# lt1345.net
KiCad netlist of a schematic drawn in EAGLE
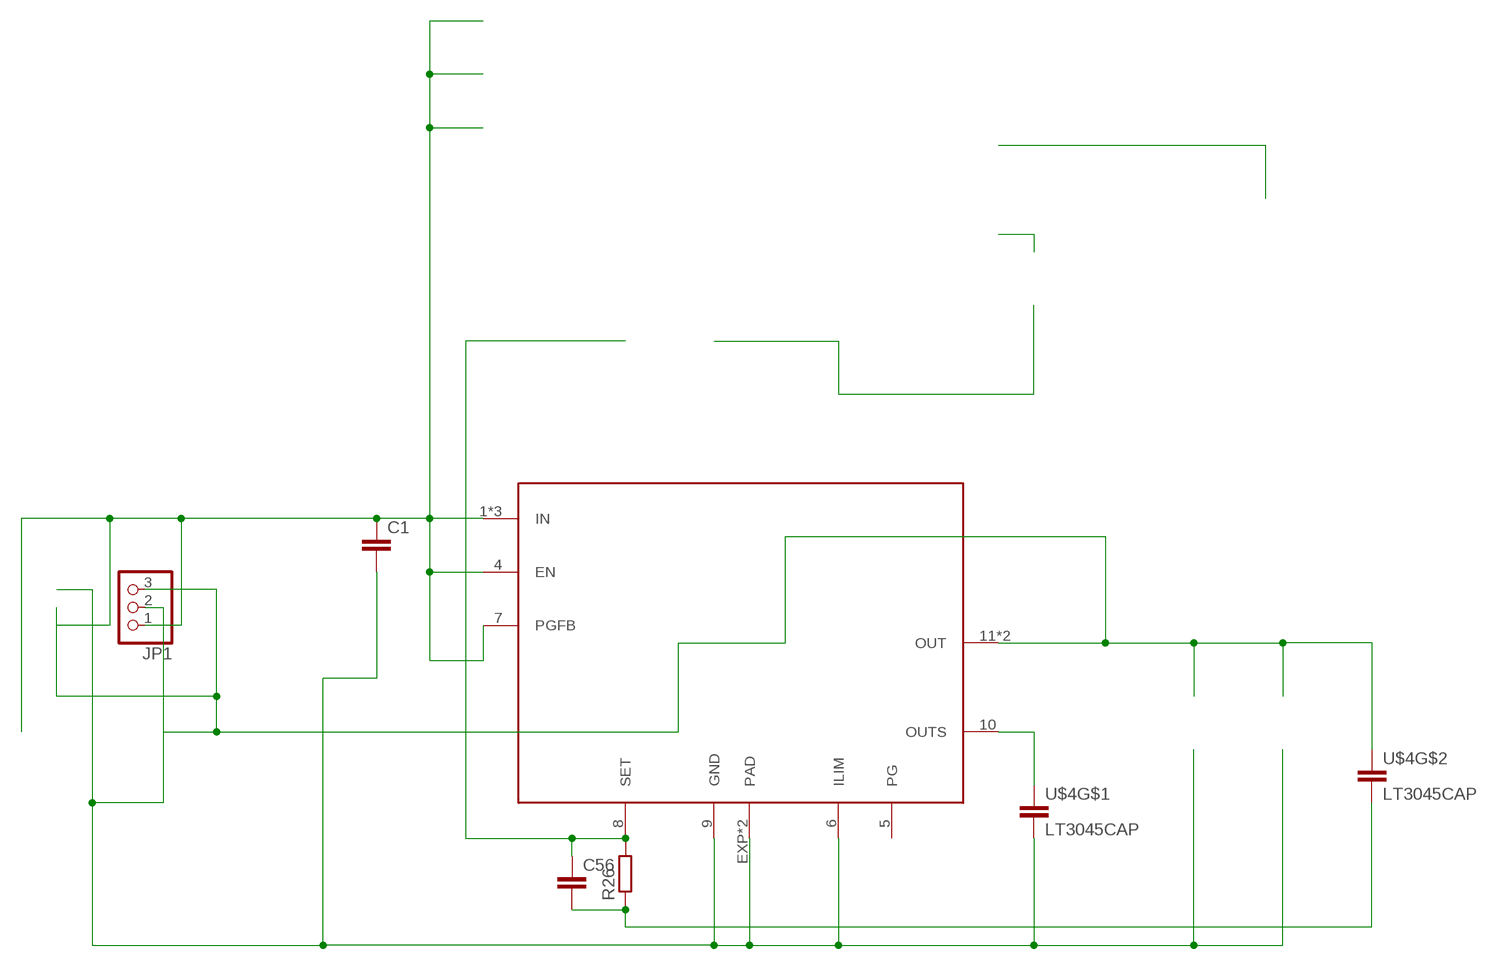
[diagram p0: schematic, sheet 1]

(export (version "E")
  (design (tool "Eeschema 10.0.6"))
  (components
    (comp (ref "C1")
      (value "C-EUC1206")
      (footprint "eagle-import:C1206")
      (libsource (lib "eagle-import") (part "C-EUC1206"))
    )
    (comp (ref "C56")
      (value "C-EUC0805")
      (footprint "eagle-import:C0805")
      (libsource (lib "eagle-import") (part "C-EUC0805"))
    )
    (comp (ref "JP1")
      (value "PINHD-1X3")
      (footprint "eagle-import:1X03")
      (libsource (lib "eagle-import") (part "PINHD-1X3"))
    )
    (comp (ref "R26")
      (value "R-EU_MELF0204R")
      (footprint "eagle-import:MINI_MELF-0204R")
      (libsource (lib "eagle-import") (part "R-EU_MELF0204R"))
    )
    (comp (ref "U$2")
      (value "LT3045")
      (footprint "eagle-import:MSOP12")
      (libsource (lib "eagle-import") (part "LT3045"))
    )
    (comp (ref "U$4")
      (value "LT3045CAP")
      (footprint "eagle-import:LT3045CAP")
      (libsource (lib "eagle-import") (part "LT3045CAP"))
    )
  )
  (nets
    (net (code "1") (name "Net-(U$2-EN)") (class "Default")
      (node (ref "C1") (pin "1") (pinfunction "1_1") (pintype "passive"))
      (node (ref "JP1") (pin "1") (pinfunction "1_1") (pintype "passive"))
      (node (ref "U$2") (pin "1") (pinfunction "IN_1") (pintype "bidirectional"))
      (node (ref "U$2") (pin "2") (pinfunction "IN_2") (pintype "bidirectional"))
      (node (ref "U$2") (pin "3") (pinfunction "IN_3") (pintype "bidirectional"))
      (node (ref "U$2") (pin "4") (pinfunction "EN_4") (pintype "bidirectional"))
      (node (ref "U$2") (pin "7") (pinfunction "PGFB_7") (pintype "bidirectional"))
    )
    (net (code "2") (name "Net-(U$2-GND)") (class "Default")
      (node (ref "C1") (pin "2") (pinfunction "2_2") (pintype "passive"))
      (node (ref "JP1") (pin "2") (pinfunction "2_2") (pintype "passive"))
      (node (ref "U$2") (pin "6") (pinfunction "ILIM_6") (pintype "bidirectional"))
      (node (ref "U$2") (pin "9") (pinfunction "GND_9") (pintype "bidirectional"))
      (node (ref "U$2") (pin "EXP") (pinfunction "PAD_EXP") (pintype "bidirectional"))
      (node (ref "U$2") (pin "EXP1") (pinfunction "PAD_EXP1") (pintype "bidirectional"))
      (node (ref "U$4") (pin "5") (pinfunction "2_5") (pintype "passive"))
    )
    (net (code "3") (name "Net-(U$2-OUTS)") (class "Default")
      (node (ref "U$2") (pin "10") (pinfunction "OUTS_10") (pintype "bidirectional"))
      (node (ref "U$4") (pin "3") (pinfunction "1_3") (pintype "passive"))
    )
    (net (code "4") (name "Net-(U$2-SET)") (class "Default")
      (node (ref "C56") (pin "1") (pinfunction "1_1") (pintype "passive"))
      (node (ref "R26") (pin "2") (pinfunction "2_2") (pintype "passive"))
      (node (ref "U$2") (pin "8") (pinfunction "SET_8") (pintype "bidirectional"))
    )
    (net (code "5") (name "Net-(U$4B-1)") (class "Default")
      (node (ref "JP1") (pin "3") (pinfunction "3_3") (pintype "passive"))
      (node (ref "U$2") (pin "11") (pinfunction "OUT_11") (pintype "bidirectional"))
      (node (ref "U$2") (pin "12") (pinfunction "OUT_12") (pintype "bidirectional"))
      (node (ref "U$4") (pin "4") (pinfunction "1_4") (pintype "passive"))
    )
    (net (code "6") (name "Net-(U$4B-2)") (class "Default")
      (node (ref "C56") (pin "2") (pinfunction "2_2") (pintype "passive"))
      (node (ref "R26") (pin "1") (pinfunction "1_1") (pintype "passive"))
      (node (ref "U$4") (pin "6") (pinfunction "2_6") (pintype "passive"))
    )
    (net (code "7") (name "unconnected-(U$2-PG-Pad5)") (class "Default")
      (node (ref "U$2") (pin "5") (pinfunction "PG_5") (pintype "bidirectional"))
    )
  )
)
